# reg.net
KiCad netlist of a schematic drawn in EAGLE
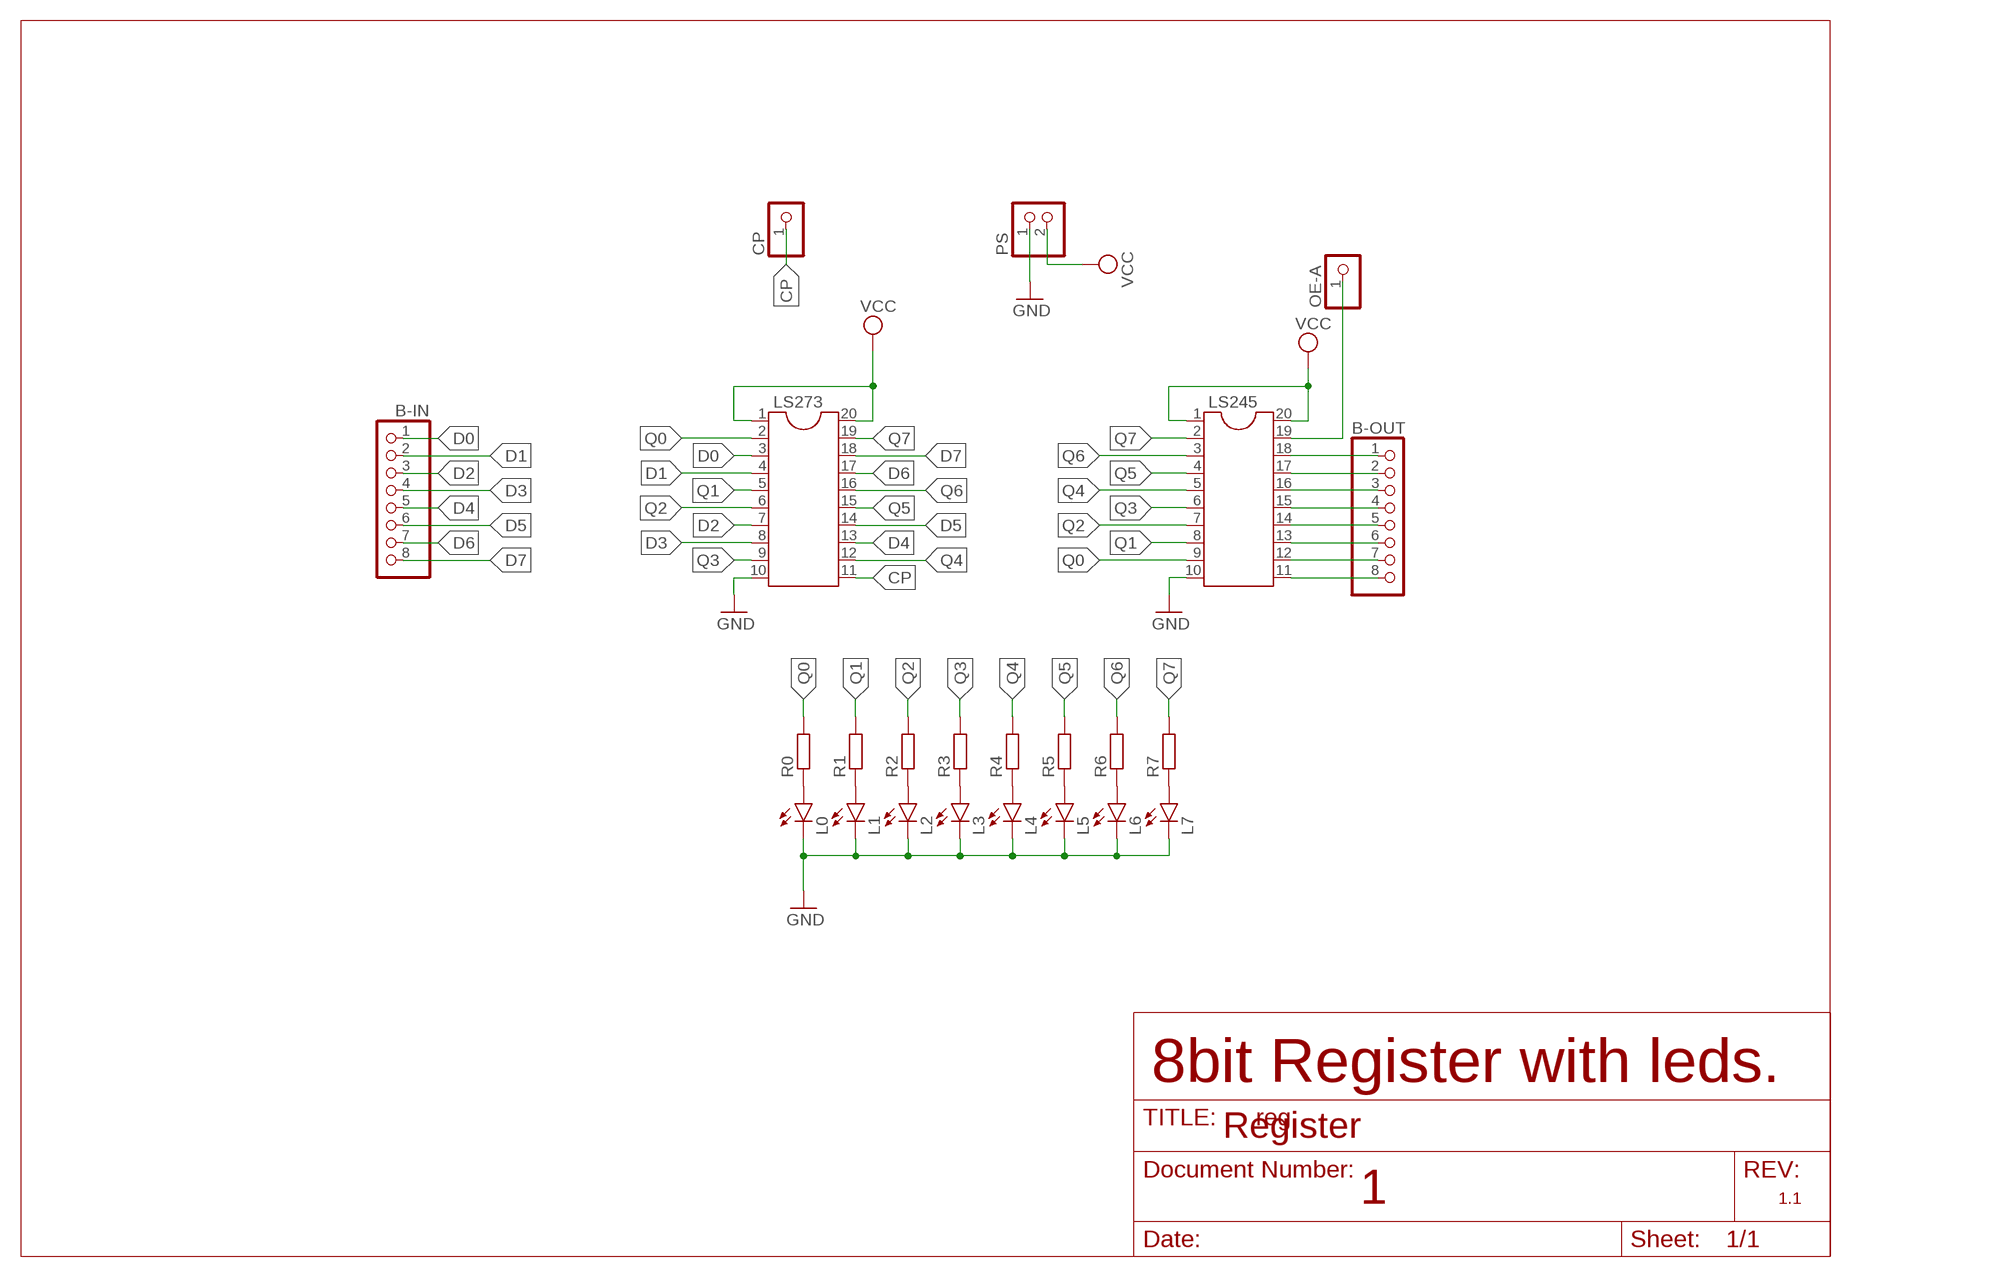
[diagram p0: schematic, sheet 1]

(export (version "E")
  (design (tool "Eeschema 10.0.6"))
  (components
    (comp (ref "B-IN")
      (value "PINHD-1X8")
      (footprint "eagle-import:1X08")
      (libsource (lib "eagle-import") (part "PINHD-1X8"))
    )
    (comp (ref "B-OUT")
      (value "PINHD-1X8")
      (footprint "eagle-import:1X08")
      (libsource (lib "eagle-import") (part "PINHD-1X8"))
    )
    (comp (ref "CP")
      (value "PINHD-1X1")
      (footprint "eagle-import:1X01")
      (libsource (lib "eagle-import") (part "PINHD-1X1"))
    )
    (comp (ref "L0")
      (value "LED5MM")
      (footprint "eagle-import:LED5MM")
      (libsource (lib "eagle-import") (part "LED5MM"))
    )
    (comp (ref "L1")
      (value "LED5MM")
      (footprint "eagle-import:LED5MM")
      (libsource (lib "eagle-import") (part "LED5MM"))
    )
    (comp (ref "L2")
      (value "LED5MM")
      (footprint "eagle-import:LED5MM")
      (libsource (lib "eagle-import") (part "LED5MM"))
    )
    (comp (ref "L3")
      (value "LED5MM")
      (footprint "eagle-import:LED5MM")
      (libsource (lib "eagle-import") (part "LED5MM"))
    )
    (comp (ref "L4")
      (value "LED5MM")
      (footprint "eagle-import:LED5MM")
      (libsource (lib "eagle-import") (part "LED5MM"))
    )
    (comp (ref "L5")
      (value "LED5MM")
      (footprint "eagle-import:LED5MM")
      (libsource (lib "eagle-import") (part "LED5MM"))
    )
    (comp (ref "L6")
      (value "LED5MM")
      (footprint "eagle-import:LED5MM")
      (libsource (lib "eagle-import") (part "LED5MM"))
    )
    (comp (ref "L7")
      (value "LED5MM")
      (footprint "eagle-import:LED5MM")
      (libsource (lib "eagle-import") (part "LED5MM"))
    )
    (comp (ref "LS245")
      (value "DIL20S")
      (footprint "eagle-import:SOCKET-20")
      (libsource (lib "eagle-import") (part "DIL20S"))
    )
    (comp (ref "LS273")
      (value "DIL20S")
      (footprint "eagle-import:SOCKET-20")
      (libsource (lib "eagle-import") (part "DIL20S"))
    )
    (comp (ref "OE-A")
      (value "PINHD-1X1")
      (footprint "eagle-import:1X01")
      (libsource (lib "eagle-import") (part "PINHD-1X1"))
    )
    (comp (ref "PS")
      (value "PINHD-1X2")
      (footprint "eagle-import:1X02")
      (libsource (lib "eagle-import") (part "PINHD-1X2"))
    )
    (comp (ref "R0")
      (value "R-EU_0204/7")
      (footprint "eagle-import:0204_7")
      (libsource (lib "eagle-import") (part "R-EU_0204/7"))
    )
    (comp (ref "R1")
      (value "R-EU_0204/7")
      (footprint "eagle-import:0204_7")
      (libsource (lib "eagle-import") (part "R-EU_0204/7"))
    )
    (comp (ref "R2")
      (value "R-EU_0204/7")
      (footprint "eagle-import:0204_7")
      (libsource (lib "eagle-import") (part "R-EU_0204/7"))
    )
    (comp (ref "R3")
      (value "R-EU_0204/7")
      (footprint "eagle-import:0204_7")
      (libsource (lib "eagle-import") (part "R-EU_0204/7"))
    )
    (comp (ref "R4")
      (value "R-EU_0204/7")
      (footprint "eagle-import:0204_7")
      (libsource (lib "eagle-import") (part "R-EU_0204/7"))
    )
    (comp (ref "R5")
      (value "R-EU_0204/7")
      (footprint "eagle-import:0204_7")
      (libsource (lib "eagle-import") (part "R-EU_0204/7"))
    )
    (comp (ref "R6")
      (value "R-EU_0204/7")
      (footprint "eagle-import:0204_7")
      (libsource (lib "eagle-import") (part "R-EU_0204/7"))
    )
    (comp (ref "R7")
      (value "R-EU_0204/7")
      (footprint "eagle-import:0204_7")
      (libsource (lib "eagle-import") (part "R-EU_0204/7"))
    )
  )
  (nets
    (net (code "1") (name "CP") (class "Default")
      (node (ref "CP") (pin "1") (pinfunction "1_1") (pintype "passive"))
      (node (ref "LS273") (pin "11") (pinfunction "11_11") (pintype "passive"))
    )
    (net (code "2") (name "D0") (class "Default")
      (node (ref "B-IN") (pin "1") (pinfunction "1_1") (pintype "passive"))
      (node (ref "LS273") (pin "3") (pinfunction "3_3") (pintype "passive"))
    )
    (net (code "3") (name "D1") (class "Default")
      (node (ref "B-IN") (pin "2") (pinfunction "2_2") (pintype "passive"))
      (node (ref "LS273") (pin "4") (pinfunction "4_4") (pintype "passive"))
    )
    (net (code "4") (name "D2") (class "Default")
      (node (ref "B-IN") (pin "3") (pinfunction "3_3") (pintype "passive"))
      (node (ref "LS273") (pin "7") (pinfunction "7_7") (pintype "passive"))
    )
    (net (code "5") (name "D3") (class "Default")
      (node (ref "B-IN") (pin "4") (pinfunction "4_4") (pintype "passive"))
      (node (ref "LS273") (pin "8") (pinfunction "8_8") (pintype "passive"))
    )
    (net (code "6") (name "D4") (class "Default")
      (node (ref "B-IN") (pin "5") (pinfunction "5_5") (pintype "passive"))
      (node (ref "LS273") (pin "13") (pinfunction "13_13") (pintype "passive"))
    )
    (net (code "7") (name "D5") (class "Default")
      (node (ref "B-IN") (pin "6") (pinfunction "6_6") (pintype "passive"))
      (node (ref "LS273") (pin "14") (pinfunction "14_14") (pintype "passive"))
    )
    (net (code "8") (name "D6") (class "Default")
      (node (ref "B-IN") (pin "7") (pinfunction "7_7") (pintype "passive"))
      (node (ref "LS273") (pin "17") (pinfunction "17_17") (pintype "passive"))
    )
    (net (code "9") (name "D7") (class "Default")
      (node (ref "B-IN") (pin "8") (pinfunction "8_8") (pintype "passive"))
      (node (ref "LS273") (pin "18") (pinfunction "18_18") (pintype "passive"))
    )
    (net (code "10") (name "GND") (class "Default")
      (node (ref "L0") (pin "K") (pinfunction "C_K") (pintype "passive"))
      (node (ref "L1") (pin "K") (pinfunction "C_K") (pintype "passive"))
      (node (ref "L2") (pin "K") (pinfunction "C_K") (pintype "passive"))
      (node (ref "L3") (pin "K") (pinfunction "C_K") (pintype "passive"))
      (node (ref "L4") (pin "K") (pinfunction "C_K") (pintype "passive"))
      (node (ref "L5") (pin "K") (pinfunction "C_K") (pintype "passive"))
      (node (ref "L6") (pin "K") (pinfunction "C_K") (pintype "passive"))
      (node (ref "L7") (pin "K") (pinfunction "C_K") (pintype "passive"))
      (node (ref "LS245") (pin "10") (pinfunction "10_10") (pintype "passive"))
      (node (ref "LS273") (pin "10") (pinfunction "10_10") (pintype "passive"))
      (node (ref "PS") (pin "1") (pinfunction "1_1") (pintype "passive"))
    )
    (net (code "11") (name "Net-(B-OUT-Pad1)") (class "Default")
      (node (ref "B-OUT") (pin "1") (pinfunction "1_1") (pintype "passive"))
      (node (ref "LS245") (pin "18") (pinfunction "18_18") (pintype "passive"))
    )
    (net (code "12") (name "Net-(B-OUT-Pad2)") (class "Default")
      (node (ref "B-OUT") (pin "2") (pinfunction "2_2") (pintype "passive"))
      (node (ref "LS245") (pin "17") (pinfunction "17_17") (pintype "passive"))
    )
    (net (code "13") (name "Net-(B-OUT-Pad3)") (class "Default")
      (node (ref "B-OUT") (pin "3") (pinfunction "3_3") (pintype "passive"))
      (node (ref "LS245") (pin "16") (pinfunction "16_16") (pintype "passive"))
    )
    (net (code "14") (name "Net-(B-OUT-Pad4)") (class "Default")
      (node (ref "B-OUT") (pin "4") (pinfunction "4_4") (pintype "passive"))
      (node (ref "LS245") (pin "15") (pinfunction "15_15") (pintype "passive"))
    )
    (net (code "15") (name "Net-(B-OUT-Pad5)") (class "Default")
      (node (ref "B-OUT") (pin "5") (pinfunction "5_5") (pintype "passive"))
      (node (ref "LS245") (pin "14") (pinfunction "14_14") (pintype "passive"))
    )
    (net (code "16") (name "Net-(B-OUT-Pad6)") (class "Default")
      (node (ref "B-OUT") (pin "6") (pinfunction "6_6") (pintype "passive"))
      (node (ref "LS245") (pin "13") (pinfunction "13_13") (pintype "passive"))
    )
    (net (code "17") (name "Net-(B-OUT-Pad7)") (class "Default")
      (node (ref "B-OUT") (pin "7") (pinfunction "7_7") (pintype "passive"))
      (node (ref "LS245") (pin "12") (pinfunction "12_12") (pintype "passive"))
    )
    (net (code "18") (name "Net-(B-OUT-Pad8)") (class "Default")
      (node (ref "B-OUT") (pin "8") (pinfunction "8_8") (pintype "passive"))
      (node (ref "LS245") (pin "11") (pinfunction "11_11") (pintype "passive"))
    )
    (net (code "19") (name "Net-(L0-PadA)") (class "Default")
      (node (ref "L0") (pin "A") (pinfunction "A_A") (pintype "passive"))
      (node (ref "R0") (pin "1") (pinfunction "1_1") (pintype "passive"))
    )
    (net (code "20") (name "Net-(L1-PadA)") (class "Default")
      (node (ref "L1") (pin "A") (pinfunction "A_A") (pintype "passive"))
      (node (ref "R1") (pin "1") (pinfunction "1_1") (pintype "passive"))
    )
    (net (code "21") (name "Net-(L2-PadA)") (class "Default")
      (node (ref "L2") (pin "A") (pinfunction "A_A") (pintype "passive"))
      (node (ref "R2") (pin "1") (pinfunction "1_1") (pintype "passive"))
    )
    (net (code "22") (name "Net-(L3-PadA)") (class "Default")
      (node (ref "L3") (pin "A") (pinfunction "A_A") (pintype "passive"))
      (node (ref "R3") (pin "1") (pinfunction "1_1") (pintype "passive"))
    )
    (net (code "23") (name "Net-(L4-PadA)") (class "Default")
      (node (ref "L4") (pin "A") (pinfunction "A_A") (pintype "passive"))
      (node (ref "R4") (pin "1") (pinfunction "1_1") (pintype "passive"))
    )
    (net (code "24") (name "Net-(L5-PadA)") (class "Default")
      (node (ref "L5") (pin "A") (pinfunction "A_A") (pintype "passive"))
      (node (ref "R5") (pin "1") (pinfunction "1_1") (pintype "passive"))
    )
    (net (code "25") (name "Net-(L6-PadA)") (class "Default")
      (node (ref "L6") (pin "A") (pinfunction "A_A") (pintype "passive"))
      (node (ref "R6") (pin "1") (pinfunction "1_1") (pintype "passive"))
    )
    (net (code "26") (name "Net-(L7-PadA)") (class "Default")
      (node (ref "L7") (pin "A") (pinfunction "A_A") (pintype "passive"))
      (node (ref "R7") (pin "1") (pinfunction "1_1") (pintype "passive"))
    )
    (net (code "27") (name "Net-(LS245-Pad19)") (class "Default")
      (node (ref "LS245") (pin "19") (pinfunction "19_19") (pintype "passive"))
      (node (ref "OE-A") (pin "1") (pinfunction "1_1") (pintype "passive"))
    )
    (net (code "28") (name "Q0") (class "Default")
      (node (ref "LS245") (pin "9") (pinfunction "9_9") (pintype "passive"))
      (node (ref "LS273") (pin "2") (pinfunction "2_2") (pintype "passive"))
      (node (ref "R0") (pin "2") (pinfunction "2_2") (pintype "passive"))
    )
    (net (code "29") (name "Q1") (class "Default")
      (node (ref "LS245") (pin "8") (pinfunction "8_8") (pintype "passive"))
      (node (ref "LS273") (pin "5") (pinfunction "5_5") (pintype "passive"))
      (node (ref "R1") (pin "2") (pinfunction "2_2") (pintype "passive"))
    )
    (net (code "30") (name "Q2") (class "Default")
      (node (ref "LS245") (pin "7") (pinfunction "7_7") (pintype "passive"))
      (node (ref "LS273") (pin "6") (pinfunction "6_6") (pintype "passive"))
      (node (ref "R2") (pin "2") (pinfunction "2_2") (pintype "passive"))
    )
    (net (code "31") (name "Q3") (class "Default")
      (node (ref "LS245") (pin "6") (pinfunction "6_6") (pintype "passive"))
      (node (ref "LS273") (pin "9") (pinfunction "9_9") (pintype "passive"))
      (node (ref "R3") (pin "2") (pinfunction "2_2") (pintype "passive"))
    )
    (net (code "32") (name "Q4") (class "Default")
      (node (ref "LS245") (pin "5") (pinfunction "5_5") (pintype "passive"))
      (node (ref "LS273") (pin "12") (pinfunction "12_12") (pintype "passive"))
      (node (ref "R4") (pin "2") (pinfunction "2_2") (pintype "passive"))
    )
    (net (code "33") (name "Q5") (class "Default")
      (node (ref "LS245") (pin "4") (pinfunction "4_4") (pintype "passive"))
      (node (ref "LS273") (pin "15") (pinfunction "15_15") (pintype "passive"))
      (node (ref "R5") (pin "2") (pinfunction "2_2") (pintype "passive"))
    )
    (net (code "34") (name "Q6") (class "Default")
      (node (ref "LS245") (pin "3") (pinfunction "3_3") (pintype "passive"))
      (node (ref "LS273") (pin "16") (pinfunction "16_16") (pintype "passive"))
      (node (ref "R6") (pin "2") (pinfunction "2_2") (pintype "passive"))
    )
    (net (code "35") (name "Q7") (class "Default")
      (node (ref "LS245") (pin "2") (pinfunction "2_2") (pintype "passive"))
      (node (ref "LS273") (pin "19") (pinfunction "19_19") (pintype "passive"))
      (node (ref "R7") (pin "2") (pinfunction "2_2") (pintype "passive"))
    )
    (net (code "36") (name "VCC") (class "Default")
      (node (ref "LS245") (pin "1") (pinfunction "1_1") (pintype "passive"))
      (node (ref "LS245") (pin "20") (pinfunction "20_20") (pintype "passive"))
      (node (ref "LS273") (pin "1") (pinfunction "1_1") (pintype "passive"))
      (node (ref "LS273") (pin "20") (pinfunction "20_20") (pintype "passive"))
      (node (ref "PS") (pin "2") (pinfunction "2_2") (pintype "passive"))
    )
  )
)
